# USB-C__TH.net
KiCad netlist of a schematic drawn in Altium Designer
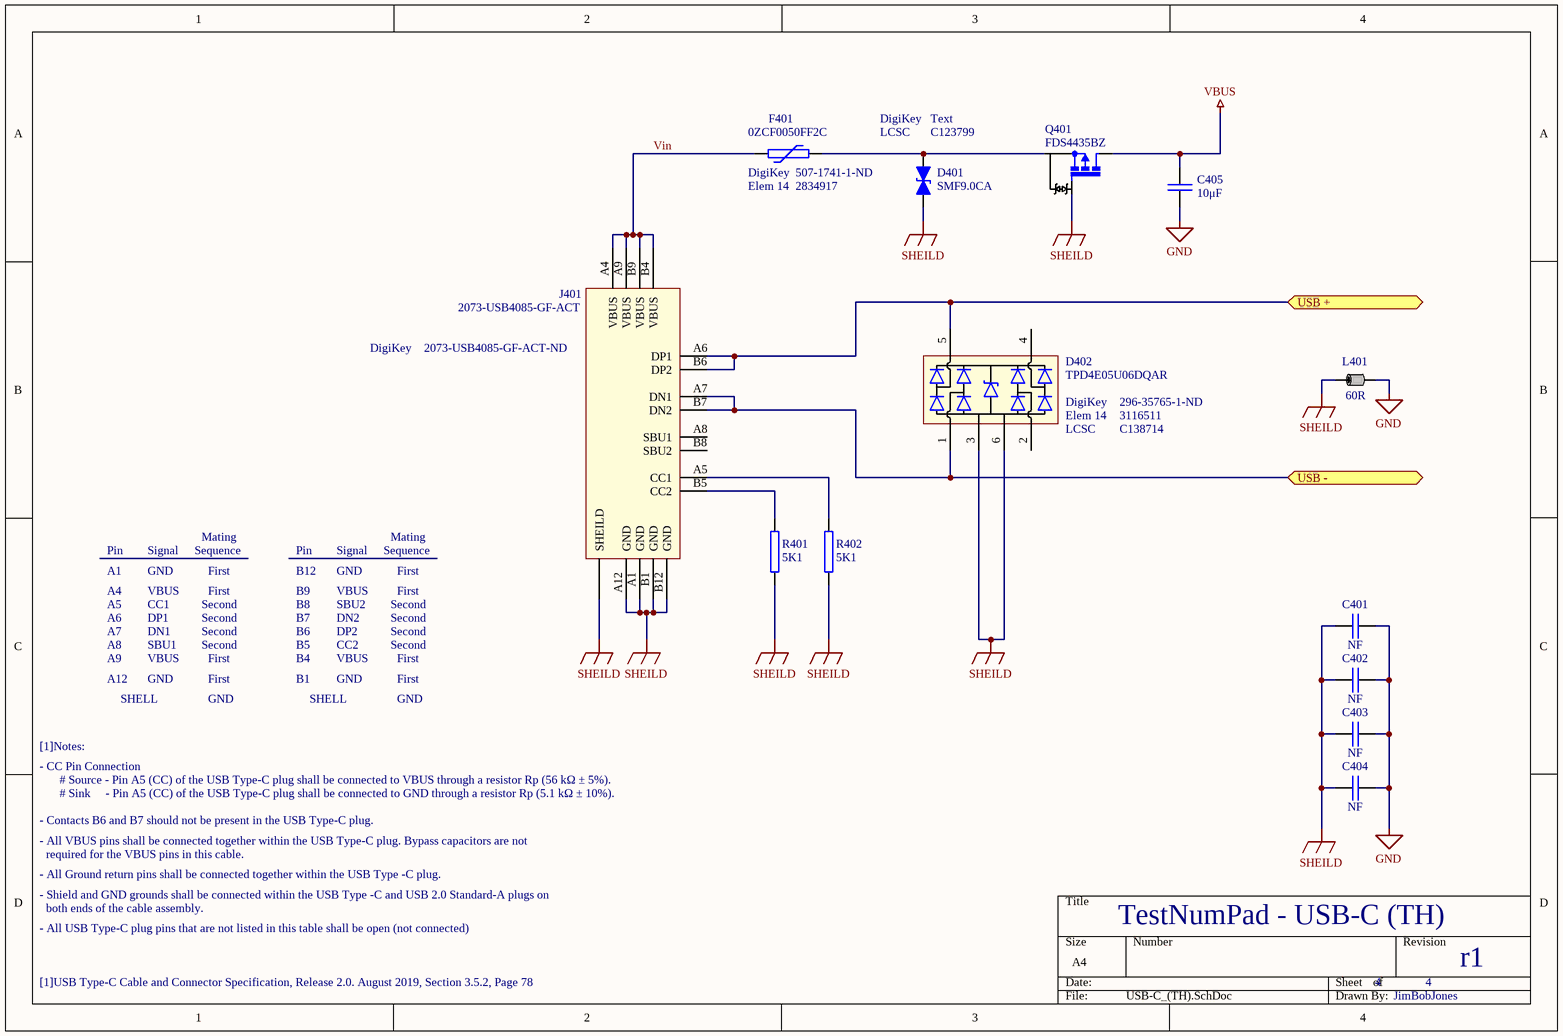
[diagram p0: USB-C_(TH).SchDoc]

(export (version "E")
  (design (tool "Eeschema 10.0.6"))
  (components
    (comp (ref "C401")
      (value "NF")
      (footprint "2012C (0805)")
      (description "2012 100nF MLCC Capacitor 50V X7R")
      (libsource (lib "JM_Keyboard") (part "2012C-100nF"))
    )
    (comp (ref "C402")
      (value "NF")
      (footprint "2012C (0805)")
      (description "2012 100nF MLCC Capacitor 50V X7R")
      (libsource (lib "JM_Keyboard") (part "2012C-100nF"))
    )
    (comp (ref "C403")
      (value "NF")
      (footprint "2012C (0805)")
      (description "2012 100nF MLCC Capacitor 50V X7R")
      (libsource (lib "JM_Keyboard") (part "2012C-100nF"))
    )
    (comp (ref "C404")
      (value "NF")
      (footprint "2012C (0805)")
      (description "2012 100nF MLCC Capacitor 50V X7R")
      (libsource (lib "JM_Keyboard") (part "2012C-100nF"))
    )
    (comp (ref "C405")
      (value "10μF")
      (footprint "3216C (1206)")
      (description "3216, 25V MLCC X5R CAPACITOR")
      (libsource (lib "JM_Keyboard") (part "3216C-10uF"))
    )
    (comp (ref "D401")
      (value "SMF9.0CA")
      (footprint "SOD-123FL")
      (description "Bi-Directional TVS Diode, Vbr 10V, Vcl 15.4V, 13A, 200W")
      (libsource (lib "JM_Keyboard") (part "Diode-TVS-SMF9.0CA"))
    )
    (comp (ref "D402")
      (value "TPD4E05U06DQAR")
      (footprint "USON-10")
      (description "TVS Array, Low Capacitance, ESD Protection, 4IO + Pwr, (<3.0pF)")
      (libsource (lib "JM_Keyboard") (part "Diode-ESD Array_1"))
    )
    (comp (ref "F401")
      (value "0ZCF0050FF2C")
      (footprint "7351 (2920)")
      (description "Ih-0.5A, It-1A, Im-100A, 60V POLYFUSE")
      (fields
        (field (name "SUPPLIER PART NUMBER 1") "507-1741-1-ND")
        (field (name "SUPPLIER PART NUMBER 2") "2834917")
      )
      (libsource (lib "JM_Keyboard") (part "Poly-miniSMDC150F"))
    )
    (comp (ref "J401")
      (value "2073-USB4085-GF-ACT")
      (footprint "USB-C (2.0,TH)")
      (description "USB 2.0 Type-C Connector, 16 Pin, TH + TH Case")
      (fields (field (name "SUPPLIER PART NUMBER 1") "2073-USB4085-GF-ACT-ND"))
      (libsource (lib "JM_Keyboard") (part "USB-C (2.0,TH)"))
    )
    (comp (ref "L401")
      (value "60R")
      (footprint "3216 (1206)")
      (description "SMD Ferrite Bead")
      (libsource (lib "JM_Keyboard") (part "FERRITE BEAD"))
    )
    (comp (ref "Q401")
      (value "FDS4435BZ")
      (footprint "SO8-150/200mil-GDS")
      (description "P-channel, 30V, 3.2A, 120-75mOhm Enhancement MOSFET with 3.8Kv ESD Protection")
      (libsource (lib "JM_Keyboard") (part "FDS4435BZ"))
    )
    (comp (ref "R401")
      (value "5K1")
      (footprint "2012R-5K1")
      (description "RESISTOR 2012 1/4 WATT THIN FILM")
      (libsource (lib "JM_Keyboard") (part "2012R-5K1"))
    )
    (comp (ref "R402")
      (value "5K1")
      (footprint "2012R-5K1")
      (description "RESISTOR 2012 1/4 WATT THIN FILM")
      (libsource (lib "JM_Keyboard") (part "2012R-5K1"))
    )
  )
  (nets
    (net (code "1") (name "/USB +") (class "Default")
      (node (ref "D402") (pin "5") (pinfunction "5_5") (pintype "passive"))
      (node (ref "J401") (pin "A6") (pinfunction "DP1_A6") (pintype "passive"))
      (node (ref "J401") (pin "B6") (pinfunction "DP2_B6") (pintype "passive"))
    )
    (net (code "2") (name "/USB -") (class "Default")
      (node (ref "D402") (pin "1") (pinfunction "1_1") (pintype "passive"))
      (node (ref "J401") (pin "A7") (pinfunction "DN1_A7") (pintype "passive"))
      (node (ref "J401") (pin "B7") (pinfunction "DN2_B7") (pintype "passive"))
    )
    (net (code "3") (name "/Vin") (class "Default")
      (node (ref "F401") (pin "1") (pinfunction "1_1") (pintype "passive"))
      (node (ref "J401") (pin "A4") (pinfunction "VBUS_A4") (pintype "passive"))
      (node (ref "J401") (pin "A9") (pinfunction "VBUS_A9") (pintype "passive"))
      (node (ref "J401") (pin "B4") (pinfunction "VBUS_B4") (pintype "passive"))
      (node (ref "J401") (pin "B9") (pinfunction "VBUS_B9") (pintype "passive"))
    )
    (net (code "4") (name "GND") (class "Default")
      (node (ref "C401") (pin "2") (pintype "passive"))
      (node (ref "C402") (pin "2") (pintype "passive"))
      (node (ref "C403") (pin "2") (pintype "passive"))
      (node (ref "C404") (pin "2") (pintype "passive"))
      (node (ref "C405") (pin "2") (pintype "passive"))
      (node (ref "L401") (pin "2") (pinfunction "2_2") (pintype "passive"))
    )
    (net (code "5") (name "Net-(D401-PadA)") (class "Default")
      (node (ref "D401") (pin "A") (pinfunction "A_A") (pintype "passive"))
      (node (ref "F401") (pin "2") (pinfunction "2_2") (pintype "passive"))
      (node (ref "Q401") (pin "S") (pinfunction "S_S") (pintype "passive"))
    )
    (net (code "6") (name "Net-(J401-CC1)") (class "Default")
      (node (ref "J401") (pin "A5") (pinfunction "CC1_A5") (pintype "passive"))
      (node (ref "R402") (pin "1") (pintype "passive"))
    )
    (net (code "7") (name "Net-(J401-CC2)") (class "Default")
      (node (ref "J401") (pin "B5") (pinfunction "CC2_B5") (pintype "passive"))
      (node (ref "R401") (pin "1") (pintype "passive"))
    )
    (net (code "8") (name "SHEILD") (class "Default")
      (node (ref "C401") (pin "1") (pintype "passive"))
      (node (ref "C402") (pin "1") (pintype "passive"))
      (node (ref "C403") (pin "1") (pintype "passive"))
      (node (ref "C404") (pin "1") (pintype "passive"))
      (node (ref "D401") (pin "K") (pinfunction "K_K") (pintype "passive"))
      (node (ref "D402") (pin "3") (pinfunction "3_3") (pintype "passive"))
      (node (ref "D402") (pin "6") (pinfunction "6_6") (pintype "passive"))
      (node (ref "J401") (pin "A1") (pinfunction "GND_A1") (pintype "passive"))
      (node (ref "J401") (pin "A12") (pinfunction "GND_A12") (pintype "passive"))
      (node (ref "J401") (pin "B1") (pinfunction "GND_B1") (pintype "passive"))
      (node (ref "J401") (pin "B12") (pinfunction "GND_B12") (pintype "passive"))
      (node (ref "J401") (pin "SHEILD") (pinfunction "SHEILD_SHEILD") (pintype "passive"))
      (node (ref "L401") (pin "1") (pinfunction "1_1") (pintype "passive"))
      (node (ref "Q401") (pin "G") (pinfunction "G_G") (pintype "passive"))
      (node (ref "R401") (pin "2") (pintype "passive"))
      (node (ref "R402") (pin "2") (pintype "passive"))
    )
    (net (code "9") (name "VBUS") (class "Default")
      (node (ref "C405") (pin "1") (pintype "passive"))
      (node (ref "Q401") (pin "D") (pinfunction "D_D") (pintype "passive"))
    )
    (net (code "10") (name "unconnected-(D402-Pad2)") (class "Default")
      (node (ref "D402") (pin "2") (pinfunction "2_2") (pintype "passive"))
    )
    (net (code "11") (name "unconnected-(D402-Pad4)") (class "Default")
      (node (ref "D402") (pin "4") (pinfunction "4_4") (pintype "passive"))
    )
    (net (code "12") (name "unconnected-(J401-SBU1-PadA8)") (class "Default")
      (node (ref "J401") (pin "A8") (pinfunction "SBU1_A8") (pintype "passive"))
    )
    (net (code "13") (name "unconnected-(J401-SBU2-PadB8)") (class "Default")
      (node (ref "J401") (pin "B8") (pinfunction "SBU2_B8") (pintype "passive"))
    )
  )
)
